# v1_0.net
KiCad netlist of a schematic drawn in Altium Designer
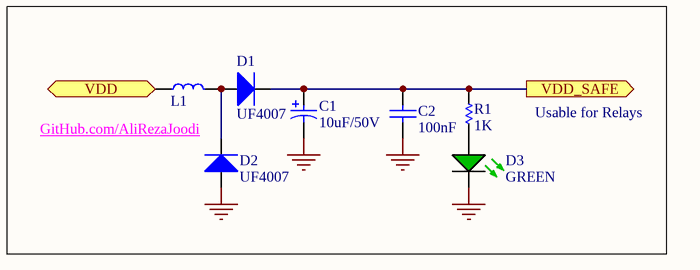
[diagram p0: v1.0.SchDoc]

(export (version "E")
  (design (tool "Eeschema 10.0.6"))
  (components
    (comp (ref "C1")
      (value "10uF/50V")
      (footprint "C_THD_EL_(P2.54-D6-H11)")
      (description "Capacitor, Electrolytic")
      (libsource (lib "Passive") (part "Capacitor_Electrolytic"))
    )
    (comp (ref "C2")
      (value "100nF")
      (footprint "C_THD_CER_(P2.54-D3.5-T1.5)")
      (description "Capacitor, Ceramic Multilayer")
      (libsource (lib "Passive") (part "Capacitor_Ceramic"))
    )
    (comp (ref "D1")
      (value "UF4007")
      (footprint "D_THD_AXIAL0.4_DO-41")
      (description "Diode,")
      (libsource (lib "Passive") (part "Diode"))
    )
    (comp (ref "D2")
      (value "UF4007")
      (footprint "D_THD_AXIAL0.4_DO-41")
      (description "Diode,")
      (libsource (lib "Passive") (part "Diode"))
    )
    (comp (ref "D3")
      (value "GREEN")
      (footprint "LED_THD_5MM_GREEN")
      (description "LED, Green")
      (fields (field (name "MANUFACTURER") "Generic Components") (field (name "PUBLISHER") "Altium Limited"))
      (libsource (lib "Display") (part "LED_GREEN"))
    )
    (comp (ref "L1")
      (value "~")
      (description "Inductor,")
      (libsource (lib "Passive") (part "Inductor_2Type"))
    )
    (comp (ref "R1")
      (value "1K")
      (footprint "R_THD_AXIAL0.4(1/4W)")
      (description "Resistor")
      (libsource (lib "Passive") (part "Resistor"))
    )
  )
  (nets
    (net (code "1") (name "/VDD") (class "Default")
      (node (ref "L1") (pin "1") (pinfunction "1_1") (pintype "passive"))
    )
    (net (code "2") (name "/VDD_SAFE") (class "Default")
      (node (ref "C1") (pin "1") (pinfunction "1_1") (pintype "passive"))
      (node (ref "C2") (pin "1") (pinfunction "1_1") (pintype "passive"))
      (node (ref "D1") (pin "2") (pinfunction "K_2") (pintype "passive"))
      (node (ref "R1") (pin "2") (pinfunction "2_2") (pintype "passive"))
    )
    (net (code "3") (name "GND") (class "Default")
      (node (ref "C1") (pin "2") (pinfunction "2_2") (pintype "passive"))
      (node (ref "C2") (pin "2") (pinfunction "2_2") (pintype "passive"))
      (node (ref "D2") (pin "1") (pinfunction "A_1") (pintype "passive"))
      (node (ref "D3") (pin "2") (pinfunction "K_2") (pintype "passive"))
    )
    (net (code "4") (name "Net-(D1-A)") (class "Default")
      (node (ref "D1") (pin "1") (pinfunction "A_1") (pintype "passive"))
      (node (ref "D2") (pin "2") (pinfunction "K_2") (pintype "passive"))
      (node (ref "L1") (pin "2") (pinfunction "2_2") (pintype "passive"))
    )
    (net (code "5") (name "Net-(D3-A)") (class "Default")
      (node (ref "D3") (pin "1") (pinfunction "A_1") (pintype "passive"))
      (node (ref "R1") (pin "1") (pinfunction "1_1") (pintype "passive"))
    )
  )
)
